# Sensor-empty-long.net
KiCad netlist of a schematic drawn in EAGLE
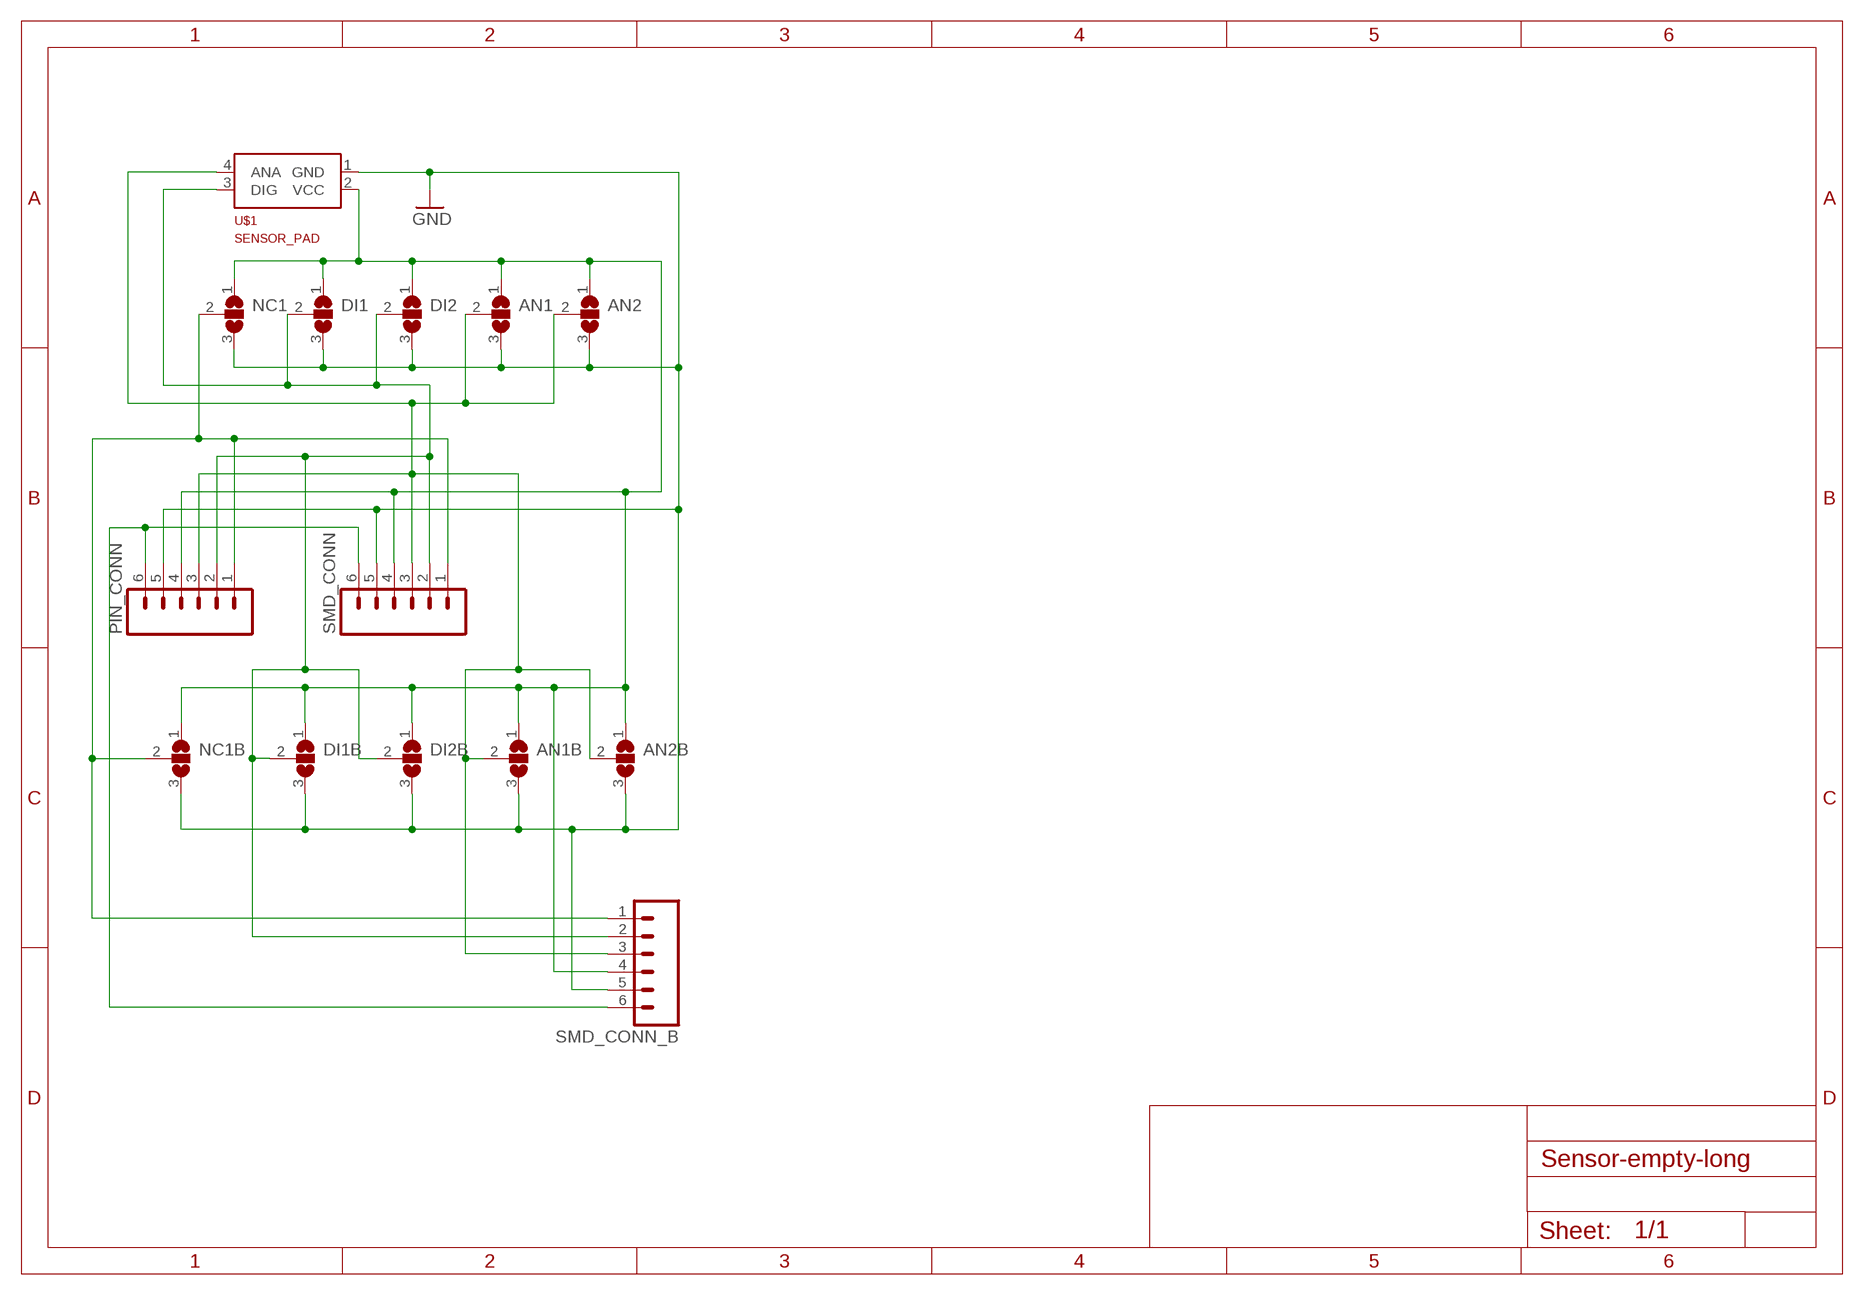
[diagram p0: schematic, sheet 1]

(export (version "E")
  (design (tool "Eeschema 10.0.6"))
  (components
    (comp (ref "AN1")
      (value "SJ2W")
      (footprint "eagle-import:SJ_2")
      (libsource (lib "eagle-import") (part "SJ2W"))
    )
    (comp (ref "AN1B")
      (value "SJ2W")
      (footprint "eagle-import:SJ_2")
      (libsource (lib "eagle-import") (part "SJ2W"))
    )
    (comp (ref "AN2")
      (value "SJ2W")
      (footprint "eagle-import:SJ_2")
      (libsource (lib "eagle-import") (part "SJ2W"))
    )
    (comp (ref "AN2B")
      (value "SJ2W")
      (footprint "eagle-import:SJ_2")
      (libsource (lib "eagle-import") (part "SJ2W"))
    )
    (comp (ref "DI1")
      (value "SJ2W")
      (footprint "eagle-import:SJ_2")
      (libsource (lib "eagle-import") (part "SJ2W"))
    )
    (comp (ref "DI1B")
      (value "SJ2W")
      (footprint "eagle-import:SJ_2")
      (libsource (lib "eagle-import") (part "SJ2W"))
    )
    (comp (ref "DI2")
      (value "SJ2W")
      (footprint "eagle-import:SJ_2")
      (libsource (lib "eagle-import") (part "SJ2W"))
    )
    (comp (ref "DI2B")
      (value "SJ2W")
      (footprint "eagle-import:SJ_2")
      (libsource (lib "eagle-import") (part "SJ2W"))
    )
    (comp (ref "NC1")
      (value "SJ2W")
      (footprint "eagle-import:SJ_2")
      (libsource (lib "eagle-import") (part "SJ2W"))
    )
    (comp (ref "NC1B")
      (value "SJ2W")
      (footprint "eagle-import:SJ_2")
      (libsource (lib "eagle-import") (part "SJ2W"))
    )
    (comp (ref "PIN_CONN")
      (value "M06SILK_FEMALE_PTH")
      (footprint "eagle-import:1X06")
      (libsource (lib "eagle-import") (part "M06SILK_FEMALE_PTH"))
    )
    (comp (ref "SMD_CONN")
      (value "M06SMD-STRAIGHT-COMBO-FEMALE")
      (footprint "eagle-import:1X06_SMD_STRAIGHT_COMBO")
      (fields (field (name "MF") "GLOBAL CONNECTOR TECHNOLOGY") (field (name "MPN") "BG306-06-A-1-0400-L-B"))
      (libsource (lib "eagle-import") (part "M06SMD-STRAIGHT-COMBO-FEMALE"))
    )
    (comp (ref "SMD_CONN_B")
      (value "M06SMD-STRAIGHT-COMBO-FEMALE")
      (footprint "eagle-import:1X06_SMD_STRAIGHT_COMBO")
      (fields (field (name "MF") "GLOBAL CONNECTOR TECHNOLOGY") (field (name "MPN") "BG306-06-A-1-0400-L-B"))
      (libsource (lib "eagle-import") (part "M06SMD-STRAIGHT-COMBO-FEMALE"))
    )
    (comp (ref "U$1")
      (value "SENSOR_PAD")
      (footprint "eagle-import:SENSOR_PAD")
      (libsource (lib "eagle-import") (part "SENSOR_PAD"))
    )
  )
  (nets
    (net (code "1") (name "GND") (class "Default")
      (node (ref "AN1") (pin "3") (pinfunction "3_3") (pintype "passive"))
      (node (ref "AN1B") (pin "3") (pinfunction "3_3") (pintype "passive"))
      (node (ref "AN2") (pin "3") (pinfunction "3_3") (pintype "passive"))
      (node (ref "AN2B") (pin "3") (pinfunction "3_3") (pintype "passive"))
      (node (ref "DI1") (pin "3") (pinfunction "3_3") (pintype "passive"))
      (node (ref "DI1B") (pin "3") (pinfunction "3_3") (pintype "passive"))
      (node (ref "DI2") (pin "3") (pinfunction "3_3") (pintype "passive"))
      (node (ref "DI2B") (pin "3") (pinfunction "3_3") (pintype "passive"))
      (node (ref "NC1") (pin "3") (pinfunction "3_3") (pintype "passive"))
      (node (ref "NC1B") (pin "3") (pinfunction "3_3") (pintype "passive"))
      (node (ref "PIN_CONN") (pin "5") (pinfunction "5_5") (pintype "passive"))
      (node (ref "SMD_CONN") (pin "5") (pinfunction "5_5") (pintype "passive"))
      (node (ref "SMD_CONN_B") (pin "5") (pinfunction "5_5") (pintype "passive"))
      (node (ref "U$1") (pin "1") (pinfunction "GND_1") (pintype "bidirectional"))
    )
    (net (code "2") (name "Net-(NC1-Pad2)") (class "Default")
      (node (ref "NC1") (pin "2") (pinfunction "2_2") (pintype "passive"))
      (node (ref "NC1B") (pin "2") (pinfunction "2_2") (pintype "passive"))
      (node (ref "PIN_CONN") (pin "1") (pinfunction "1_1") (pintype "passive"))
      (node (ref "SMD_CONN") (pin "1") (pinfunction "1_1") (pintype "passive"))
      (node (ref "SMD_CONN_B") (pin "1") (pinfunction "1_1") (pintype "passive"))
    )
    (net (code "3") (name "Net-(PIN_CONN-Pad6)") (class "Default")
      (node (ref "PIN_CONN") (pin "6") (pinfunction "6_6") (pintype "passive"))
      (node (ref "SMD_CONN") (pin "6") (pinfunction "6_6") (pintype "passive"))
      (node (ref "SMD_CONN_B") (pin "6") (pinfunction "6_6") (pintype "passive"))
    )
    (net (code "4") (name "Net-(U$1-ANA)") (class "Default")
      (node (ref "AN1") (pin "2") (pinfunction "2_2") (pintype "passive"))
      (node (ref "AN1B") (pin "2") (pinfunction "2_2") (pintype "passive"))
      (node (ref "AN2") (pin "2") (pinfunction "2_2") (pintype "passive"))
      (node (ref "AN2B") (pin "2") (pinfunction "2_2") (pintype "passive"))
      (node (ref "PIN_CONN") (pin "3") (pinfunction "3_3") (pintype "passive"))
      (node (ref "SMD_CONN") (pin "3") (pinfunction "3_3") (pintype "passive"))
      (node (ref "SMD_CONN_B") (pin "3") (pinfunction "3_3") (pintype "passive"))
      (node (ref "U$1") (pin "4") (pinfunction "ANA_4") (pintype "bidirectional"))
    )
    (net (code "5") (name "Net-(U$1-DIG)") (class "Default")
      (node (ref "DI1") (pin "2") (pinfunction "2_2") (pintype "passive"))
      (node (ref "DI1B") (pin "2") (pinfunction "2_2") (pintype "passive"))
      (node (ref "DI2") (pin "2") (pinfunction "2_2") (pintype "passive"))
      (node (ref "DI2B") (pin "2") (pinfunction "2_2") (pintype "passive"))
      (node (ref "PIN_CONN") (pin "2") (pinfunction "2_2") (pintype "passive"))
      (node (ref "SMD_CONN") (pin "2") (pinfunction "2_2") (pintype "passive"))
      (node (ref "SMD_CONN_B") (pin "2") (pinfunction "2_2") (pintype "passive"))
      (node (ref "U$1") (pin "3") (pinfunction "DIG_3") (pintype "bidirectional"))
    )
    (net (code "6") (name "Net-(U$1-VCC)") (class "Default")
      (node (ref "AN1") (pin "1") (pinfunction "1_1") (pintype "passive"))
      (node (ref "AN1B") (pin "1") (pinfunction "1_1") (pintype "passive"))
      (node (ref "AN2") (pin "1") (pinfunction "1_1") (pintype "passive"))
      (node (ref "AN2B") (pin "1") (pinfunction "1_1") (pintype "passive"))
      (node (ref "DI1") (pin "1") (pinfunction "1_1") (pintype "passive"))
      (node (ref "DI1B") (pin "1") (pinfunction "1_1") (pintype "passive"))
      (node (ref "DI2") (pin "1") (pinfunction "1_1") (pintype "passive"))
      (node (ref "DI2B") (pin "1") (pinfunction "1_1") (pintype "passive"))
      (node (ref "NC1") (pin "1") (pinfunction "1_1") (pintype "passive"))
      (node (ref "NC1B") (pin "1") (pinfunction "1_1") (pintype "passive"))
      (node (ref "PIN_CONN") (pin "4") (pinfunction "4_4") (pintype "passive"))
      (node (ref "SMD_CONN") (pin "4") (pinfunction "4_4") (pintype "passive"))
      (node (ref "SMD_CONN_B") (pin "4") (pinfunction "4_4") (pintype "passive"))
      (node (ref "U$1") (pin "2") (pinfunction "VCC_2") (pintype "bidirectional"))
    )
  )
)
